# CiroSeriale_V1.net
KiCad netlist of a schematic drawn in EAGLE
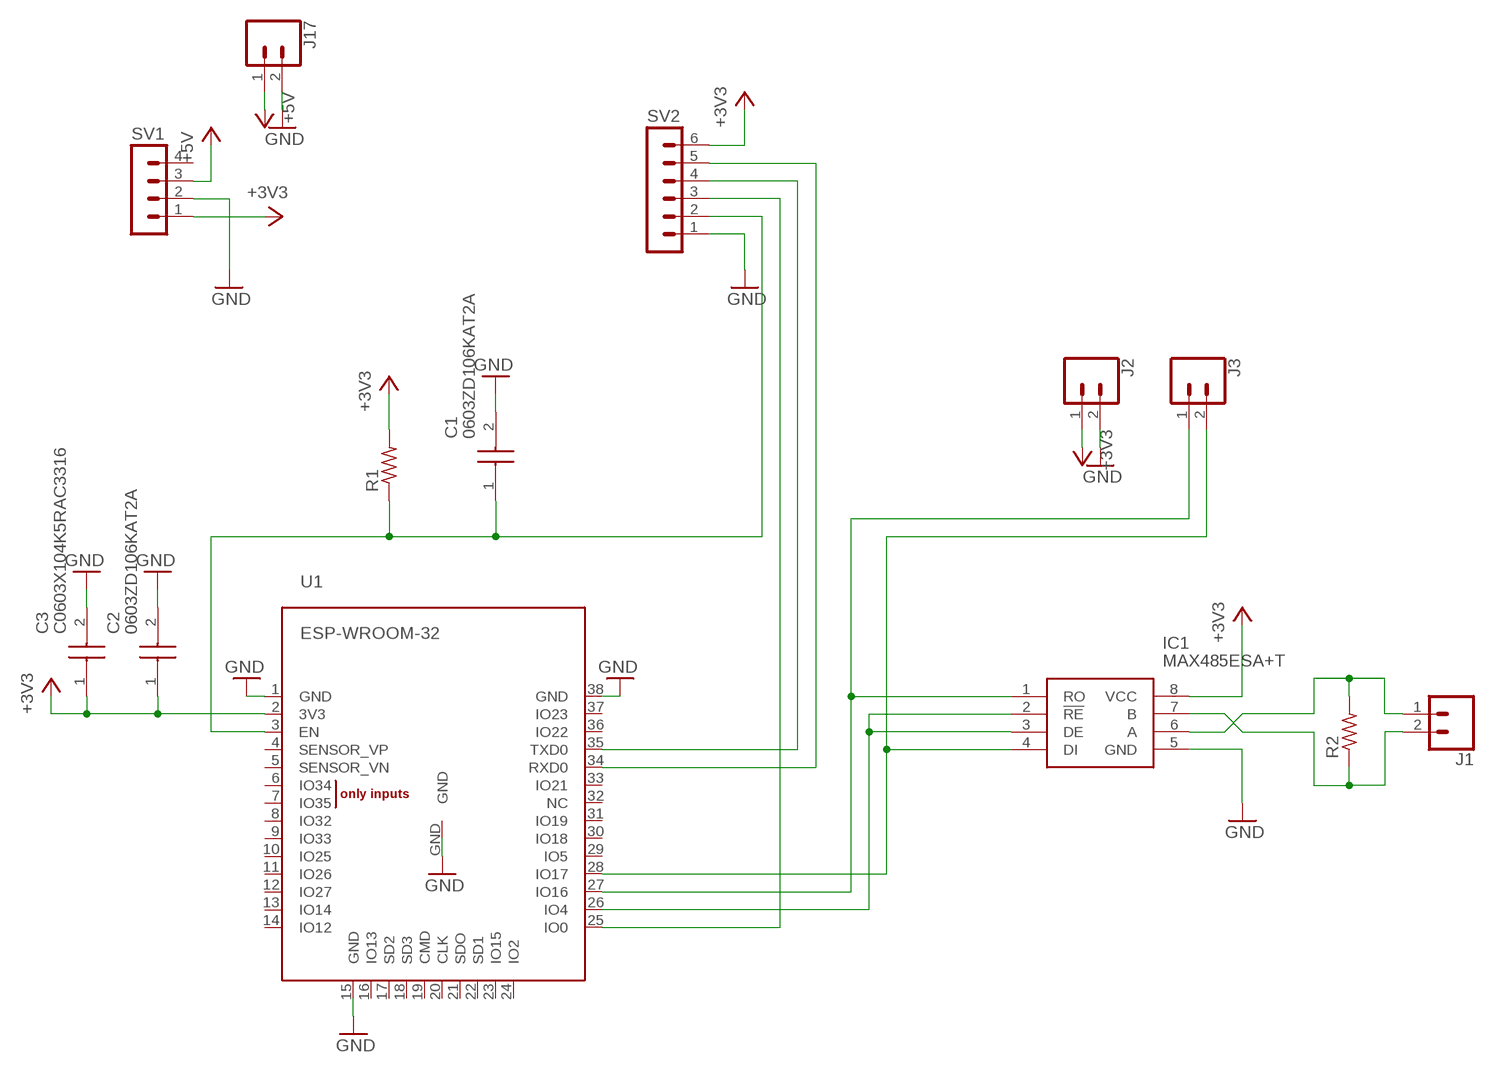
[diagram p0: schematic, sheet 1]

(export (version "E")
  (design (tool "Eeschema 10.0.6"))
  (components
    (comp (ref "C1")
      (value "0603ZD106KAT2A")
      (footprint "eagle-import:CAPC1608X90N")
      (fields (field (name "MOUSER_PART_NUMBER") "581-0603ZD106KAT2A"))
      (libsource (lib "eagle-import") (part "0603ZD106KAT2A"))
    )
    (comp (ref "C2")
      (value "0603ZD106KAT2A")
      (footprint "eagle-import:CAPC1608X90N")
      (fields (field (name "MOUSER_PART_NUMBER") "581-0603ZD106KAT2A"))
      (libsource (lib "eagle-import") (part "0603ZD106KAT2A"))
    )
    (comp (ref "C3")
      (value "C0603X104K5RAC3316")
      (footprint "eagle-import:CAPC1608X95N")
      (fields (field (name "MOUSER_PART_NUMBER") "80-C0603X104K5R3316"))
      (libsource (lib "eagle-import") (part "C0603X104K5RAC3316"))
    )
    (comp (ref "IC1")
      (value "MAX485ESA+T")
      (footprint "eagle-import:SOIC127P600X175-8N")
      (fields (field (name "MOUSER_PART_NUMBER") "700-MAX485ESAT"))
      (libsource (lib "eagle-import") (part "MAX485ESA+T"))
    )
    (comp (ref "J1")
      (value "CONN_025MM")
      (footprint "eagle-import:SCREWTERMINAL-5MM-2")
      (libsource (lib "eagle-import") (part "CONN_025MM"))
    )
    (comp (ref "J2")
      (value "CONN_025MM")
      (footprint "eagle-import:SCREWTERMINAL-5MM-2")
      (libsource (lib "eagle-import") (part "CONN_025MM"))
    )
    (comp (ref "J3")
      (value "CONN_025MM")
      (footprint "eagle-import:SCREWTERMINAL-5MM-2")
      (libsource (lib "eagle-import") (part "CONN_025MM"))
    )
    (comp (ref "J17")
      (value "CONN_025MM")
      (footprint "eagle-import:SCREWTERMINAL-5MM-2")
      (libsource (lib "eagle-import") (part "CONN_025MM"))
    )
    (comp (ref "R1")
      (value "R-US_R0603")
      (footprint "eagle-import:R0603")
      (libsource (lib "eagle-import") (part "resistor_348_R-US_R0603"))
    )
    (comp (ref "R2")
      (value "R-US_0204/7")
      (footprint "eagle-import:0204_7")
      (libsource (lib "eagle-import") (part "R-US_0204/7"))
    )
    (comp (ref "SV1")
      (value "MA04-1")
      (footprint "eagle-import:MA04-1")
      (libsource (lib "eagle-import") (part "MA04-1"))
    )
    (comp (ref "SV2")
      (value "MA06-1")
      (footprint "eagle-import:MA06-1")
      (libsource (lib "eagle-import") (part "MA06-1"))
    )
    (comp (ref "U1")
      (value "ESP-WROOM-32")
      (footprint "eagle-import:ESP-WROOM-32")
      (libsource (lib "eagle-import") (part "ESP-WROOM-32"))
    )
  )
  (nets
    (net (code "1") (name "+3V3") (class "Default")
      (node (ref "C2") (pin "1") (pinfunction "1_1") (pintype "bidirectional"))
      (node (ref "C3") (pin "1") (pinfunction "1_1") (pintype "bidirectional"))
      (node (ref "IC1") (pin "8") (pinfunction "VCC_8") (pintype "bidirectional"))
      (node (ref "J2") (pin "1") (pinfunction "1_1") (pintype "passive"))
      (node (ref "R1") (pin "2") (pinfunction "2_2") (pintype "passive"))
      (node (ref "SV1") (pin "1") (pinfunction "1_1") (pintype "passive"))
      (node (ref "SV2") (pin "6") (pinfunction "6_6") (pintype "passive"))
      (node (ref "U1") (pin "2") (pinfunction "3V3_2") (pintype "bidirectional"))
    )
    (net (code "2") (name "+5V") (class "Default")
      (node (ref "J17") (pin "1") (pinfunction "1_1") (pintype "passive"))
      (node (ref "SV1") (pin "3") (pinfunction "3_3") (pintype "passive"))
    )
    (net (code "3") (name "GND") (class "Default")
      (node (ref "C1") (pin "2") (pinfunction "2_2") (pintype "bidirectional"))
      (node (ref "C2") (pin "2") (pinfunction "2_2") (pintype "bidirectional"))
      (node (ref "C3") (pin "2") (pinfunction "2_2") (pintype "bidirectional"))
      (node (ref "IC1") (pin "5") (pinfunction "GND_5") (pintype "bidirectional"))
      (node (ref "J17") (pin "2") (pinfunction "2_2") (pintype "passive"))
      (node (ref "J2") (pin "2") (pinfunction "2_2") (pintype "passive"))
      (node (ref "SV1") (pin "2") (pinfunction "2_2") (pintype "passive"))
      (node (ref "SV2") (pin "1") (pinfunction "1_1") (pintype "passive"))
      (node (ref "U1") (pin "1") (pinfunction "GND_1") (pintype "bidirectional"))
      (node (ref "U1") (pin "15") (pinfunction "GND_15") (pintype "bidirectional"))
      (node (ref "U1") (pin "38") (pinfunction "GND_38") (pintype "bidirectional"))
      (node (ref "U1") (pin "GND") (pinfunction "GND_GND") (pintype "bidirectional"))
    )
    (net (code "4") (name "Net-(IC1-A)") (class "Default")
      (node (ref "IC1") (pin "6") (pinfunction "A_6") (pintype "bidirectional"))
      (node (ref "J1") (pin "1") (pinfunction "1_1") (pintype "passive"))
      (node (ref "R2") (pin "2") (pinfunction "2_2") (pintype "passive"))
    )
    (net (code "5") (name "Net-(IC1-B)") (class "Default")
      (node (ref "IC1") (pin "7") (pinfunction "B_7") (pintype "bidirectional"))
      (node (ref "J1") (pin "2") (pinfunction "2_2") (pintype "passive"))
      (node (ref "R2") (pin "1") (pinfunction "1_1") (pintype "passive"))
    )
    (net (code "6") (name "Net-(IC1-DE)") (class "Default")
      (node (ref "IC1") (pin "2") (pinfunction "~{RE}_2") (pintype "bidirectional"))
      (node (ref "IC1") (pin "3") (pinfunction "DE_3") (pintype "bidirectional"))
      (node (ref "U1") (pin "26") (pinfunction "IO4_26") (pintype "bidirectional"))
    )
    (net (code "7") (name "Net-(IC1-DI)") (class "Default")
      (node (ref "IC1") (pin "4") (pinfunction "DI_4") (pintype "bidirectional"))
      (node (ref "J3") (pin "2") (pinfunction "2_2") (pintype "passive"))
      (node (ref "U1") (pin "28") (pinfunction "IO17_28") (pintype "bidirectional"))
    )
    (net (code "8") (name "Net-(IC1-RO)") (class "Default")
      (node (ref "IC1") (pin "1") (pinfunction "RO_1") (pintype "bidirectional"))
      (node (ref "J3") (pin "1") (pinfunction "1_1") (pintype "passive"))
      (node (ref "U1") (pin "27") (pinfunction "IO16_27") (pintype "bidirectional"))
    )
    (net (code "9") (name "Net-(U1-EN)") (class "Default")
      (node (ref "C1") (pin "1") (pinfunction "1_1") (pintype "bidirectional"))
      (node (ref "R1") (pin "1") (pinfunction "1_1") (pintype "passive"))
      (node (ref "SV2") (pin "2") (pinfunction "2_2") (pintype "passive"))
      (node (ref "U1") (pin "3") (pinfunction "EN_3") (pintype "bidirectional"))
    )
    (net (code "10") (name "Net-(U1-IO0)") (class "Default")
      (node (ref "SV2") (pin "3") (pinfunction "3_3") (pintype "passive"))
      (node (ref "U1") (pin "25") (pinfunction "IO0_25") (pintype "bidirectional"))
    )
    (net (code "11") (name "Net-(U1-RXD0)") (class "Default")
      (node (ref "SV2") (pin "5") (pinfunction "5_5") (pintype "passive"))
      (node (ref "U1") (pin "34") (pinfunction "RXD0_34") (pintype "bidirectional"))
    )
    (net (code "12") (name "Net-(U1-TXD0)") (class "Default")
      (node (ref "SV2") (pin "4") (pinfunction "4_4") (pintype "passive"))
      (node (ref "U1") (pin "35") (pinfunction "TXD0_35") (pintype "bidirectional"))
    )
    (net (code "13") (name "unconnected-(SV1-Pad4)") (class "Default")
      (node (ref "SV1") (pin "4") (pinfunction "4_4") (pintype "passive"))
    )
    (net (code "14") (name "unconnected-(U1-CLK-Pad20)") (class "Default")
      (node (ref "U1") (pin "20") (pinfunction "CLK_20") (pintype "bidirectional"))
    )
    (net (code "15") (name "unconnected-(U1-CMD-Pad19)") (class "Default")
      (node (ref "U1") (pin "19") (pinfunction "CMD_19") (pintype "bidirectional"))
    )
    (net (code "16") (name "unconnected-(U1-IO2-Pad24)") (class "Default")
      (node (ref "U1") (pin "24") (pinfunction "IO2_24") (pintype "bidirectional"))
    )
    (net (code "17") (name "unconnected-(U1-IO5-Pad29)") (class "Default")
      (node (ref "U1") (pin "29") (pinfunction "IO5_29") (pintype "bidirectional"))
    )
    (net (code "18") (name "unconnected-(U1-IO12-Pad14)") (class "Default")
      (node (ref "U1") (pin "14") (pinfunction "IO12_14") (pintype "bidirectional"))
    )
    (net (code "19") (name "unconnected-(U1-IO13-Pad16)") (class "Default")
      (node (ref "U1") (pin "16") (pinfunction "IO13_16") (pintype "bidirectional"))
    )
    (net (code "20") (name "unconnected-(U1-IO14-Pad13)") (class "Default")
      (node (ref "U1") (pin "13") (pinfunction "IO14_13") (pintype "bidirectional"))
    )
    (net (code "21") (name "unconnected-(U1-IO15-Pad23)") (class "Default")
      (node (ref "U1") (pin "23") (pinfunction "IO15_23") (pintype "bidirectional"))
    )
    (net (code "22") (name "unconnected-(U1-IO18-Pad30)") (class "Default")
      (node (ref "U1") (pin "30") (pinfunction "IO18_30") (pintype "bidirectional"))
    )
    (net (code "23") (name "unconnected-(U1-IO19-Pad31)") (class "Default")
      (node (ref "U1") (pin "31") (pinfunction "IO19_31") (pintype "bidirectional"))
    )
    (net (code "24") (name "unconnected-(U1-IO21-Pad33)") (class "Default")
      (node (ref "U1") (pin "33") (pinfunction "IO21_33") (pintype "bidirectional"))
    )
    (net (code "25") (name "unconnected-(U1-IO22-Pad36)") (class "Default")
      (node (ref "U1") (pin "36") (pinfunction "IO22_36") (pintype "bidirectional"))
    )
    (net (code "26") (name "unconnected-(U1-IO23-Pad37)") (class "Default")
      (node (ref "U1") (pin "37") (pinfunction "IO23_37") (pintype "bidirectional"))
    )
    (net (code "27") (name "unconnected-(U1-IO25-Pad10)") (class "Default")
      (node (ref "U1") (pin "10") (pinfunction "IO25_10") (pintype "bidirectional"))
    )
    (net (code "28") (name "unconnected-(U1-IO26-Pad11)") (class "Default")
      (node (ref "U1") (pin "11") (pinfunction "IO26_11") (pintype "bidirectional"))
    )
    (net (code "29") (name "unconnected-(U1-IO27-Pad12)") (class "Default")
      (node (ref "U1") (pin "12") (pinfunction "IO27_12") (pintype "bidirectional"))
    )
    (net (code "30") (name "unconnected-(U1-IO32-Pad8)") (class "Default")
      (node (ref "U1") (pin "8") (pinfunction "IO32_8") (pintype "bidirectional"))
    )
    (net (code "31") (name "unconnected-(U1-IO33-Pad9)") (class "Default")
      (node (ref "U1") (pin "9") (pinfunction "IO33_9") (pintype "bidirectional"))
    )
    (net (code "32") (name "unconnected-(U1-IO34-Pad6)") (class "Default")
      (node (ref "U1") (pin "6") (pinfunction "IO34_6") (pintype "input"))
    )
    (net (code "33") (name "unconnected-(U1-IO35-Pad7)") (class "Default")
      (node (ref "U1") (pin "7") (pinfunction "IO35_7") (pintype "input"))
    )
    (net (code "34") (name "unconnected-(U1-NC-Pad32)") (class "Default")
      (node (ref "U1") (pin "32") (pinfunction "NC_32") (pintype "bidirectional"))
    )
    (net (code "35") (name "unconnected-(U1-SD1-Pad22)") (class "Default")
      (node (ref "U1") (pin "22") (pinfunction "SD1_22") (pintype "bidirectional"))
    )
    (net (code "36") (name "unconnected-(U1-SD2-Pad17)") (class "Default")
      (node (ref "U1") (pin "17") (pinfunction "SD2_17") (pintype "bidirectional"))
    )
    (net (code "37") (name "unconnected-(U1-SD3-Pad18)") (class "Default")
      (node (ref "U1") (pin "18") (pinfunction "SD3_18") (pintype "bidirectional"))
    )
    (net (code "38") (name "unconnected-(U1-SDO-Pad21)") (class "Default")
      (node (ref "U1") (pin "21") (pinfunction "SDO_21") (pintype "bidirectional"))
    )
    (net (code "39") (name "unconnected-(U1-SENSOR_VN-Pad5)") (class "Default")
      (node (ref "U1") (pin "5") (pinfunction "SENSOR_VN_5") (pintype "input"))
    )
    (net (code "40") (name "unconnected-(U1-SENSOR_VP-Pad4)") (class "Default")
      (node (ref "U1") (pin "4") (pinfunction "SENSOR_VP_4") (pintype "input"))
    )
  )
)
